# regulator_plus_switch.net
KiCad netlist of a schematic drawn in EAGLE
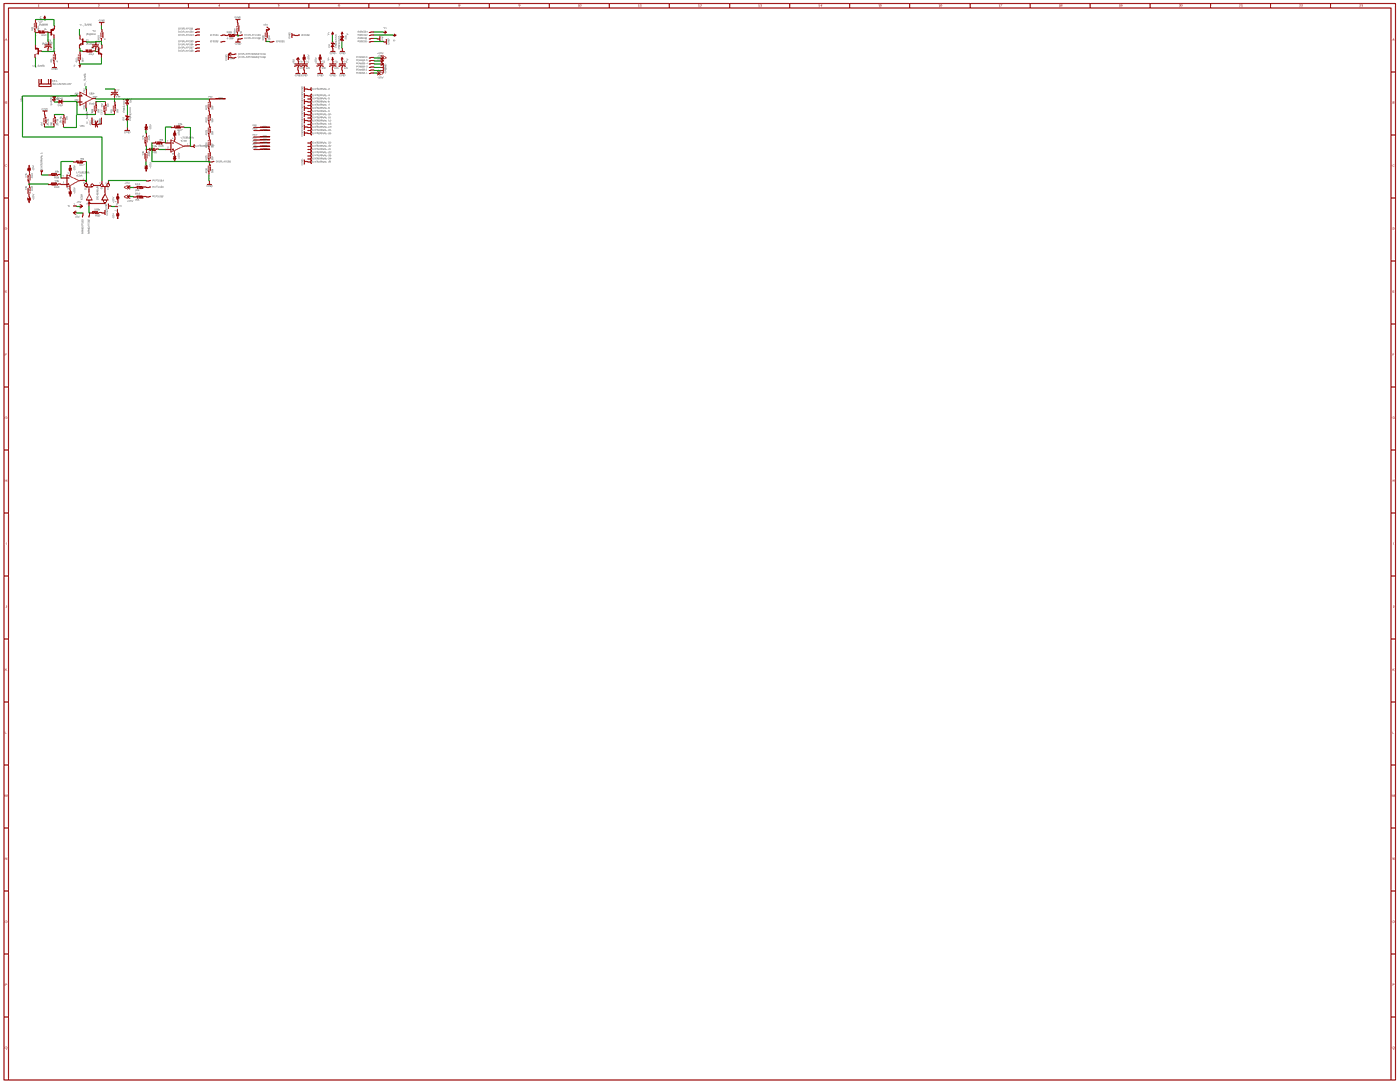
[diagram p0: schematic, sheet 1, overview]
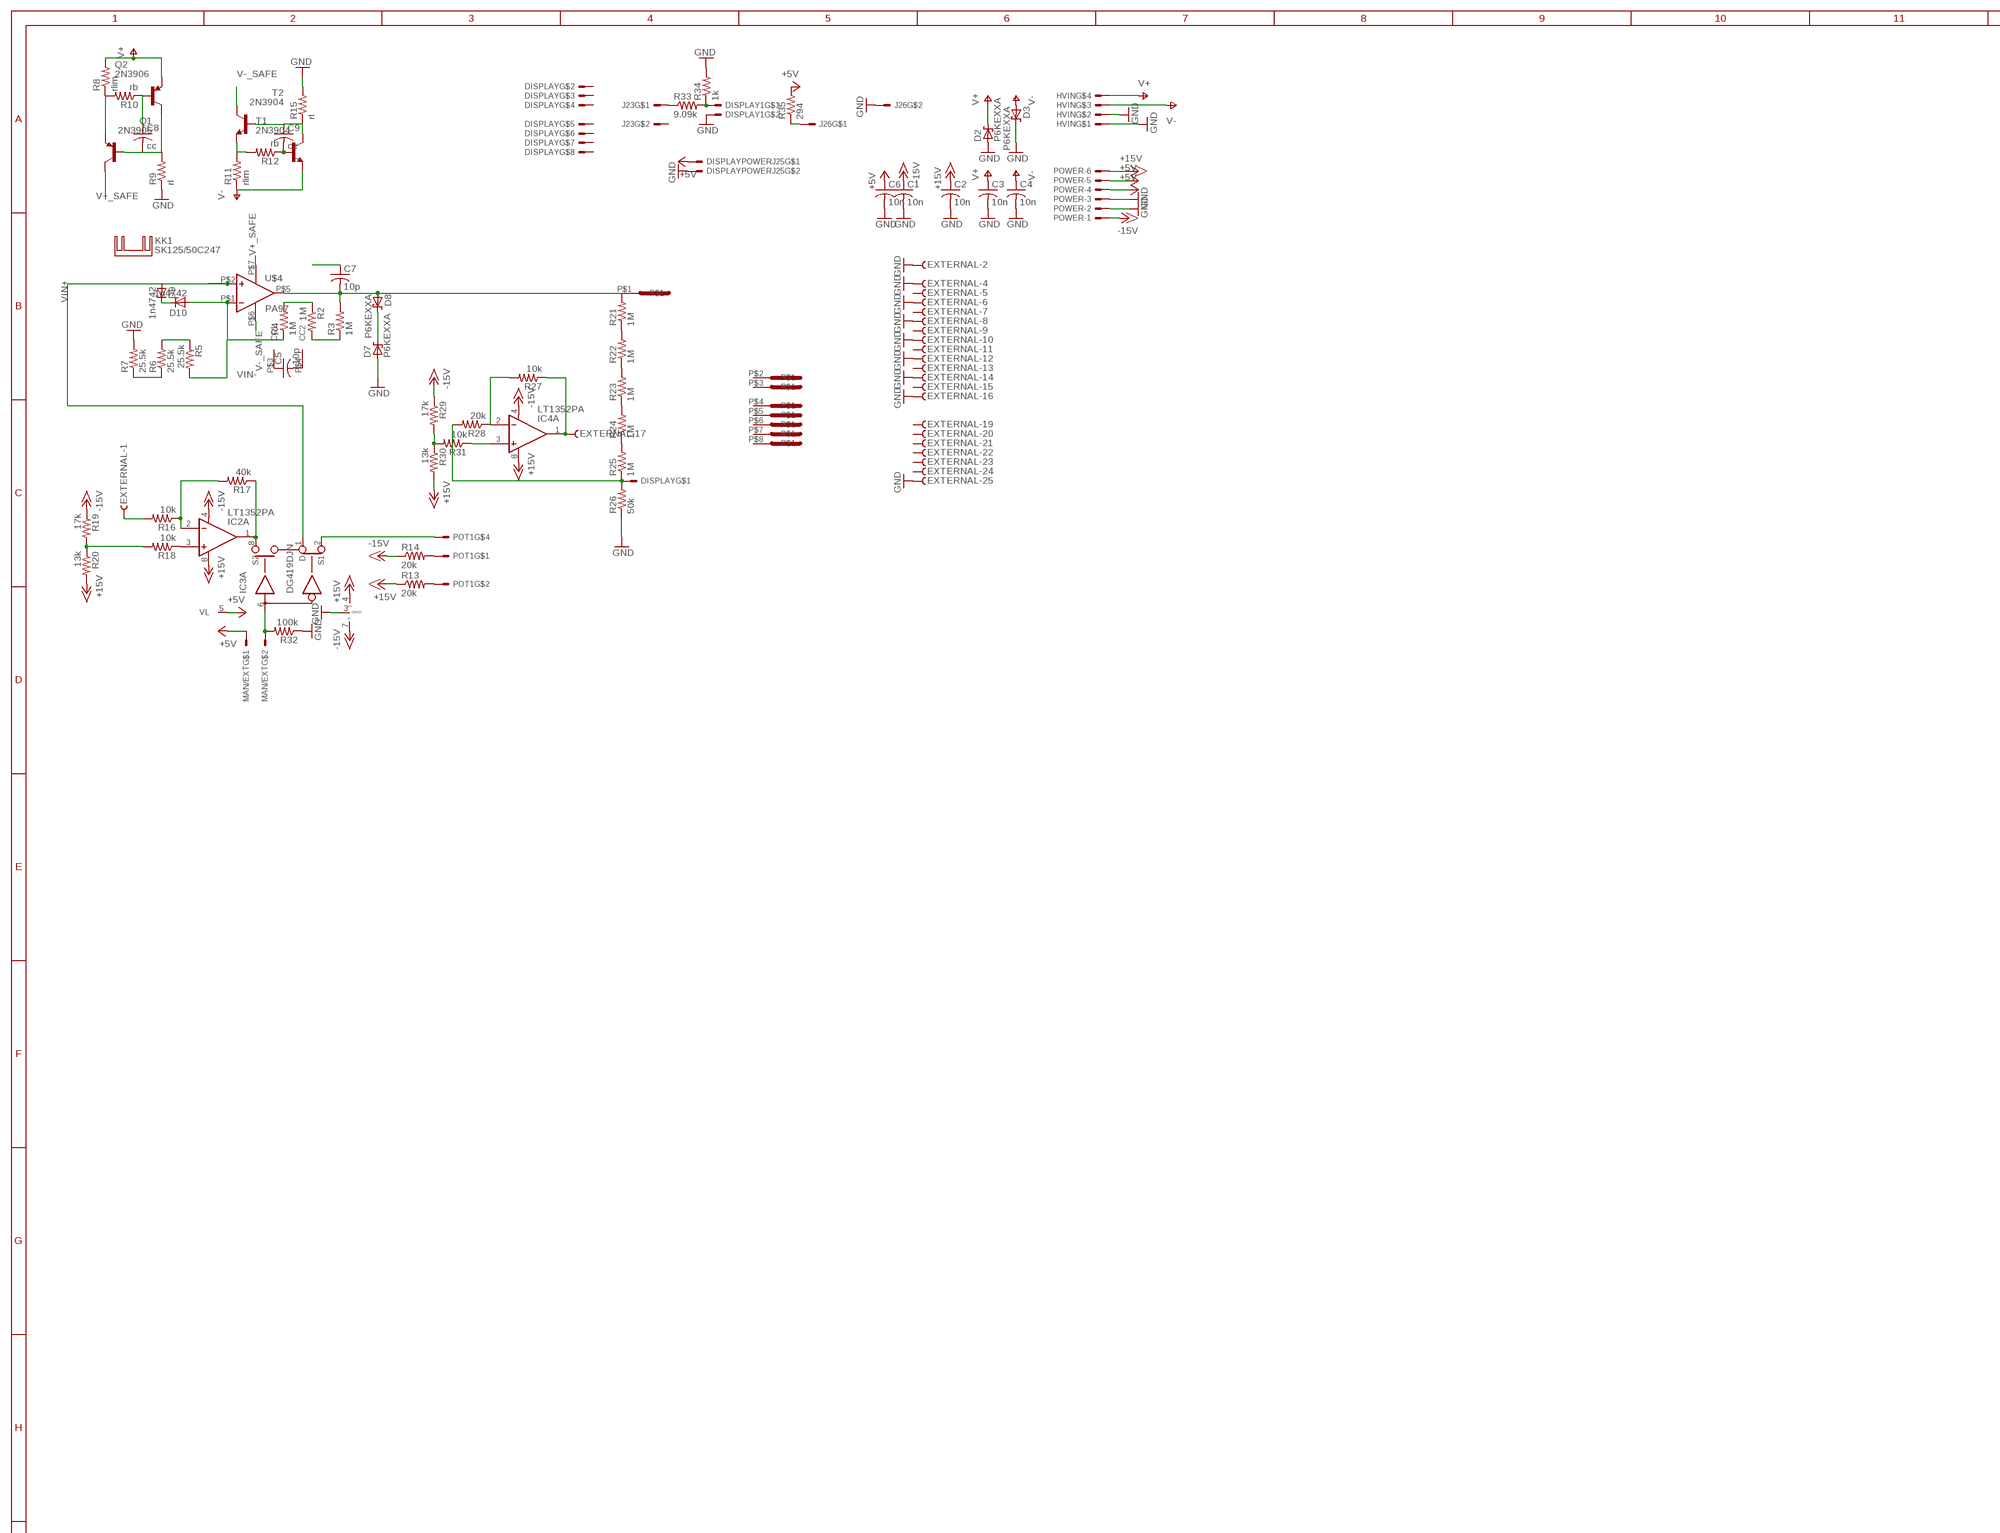
[diagram p1: schematic, sheet 1, part 1 of 5]
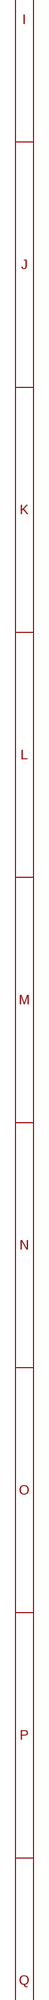
[diagram p2: schematic, sheet 1, part 2 of 5]
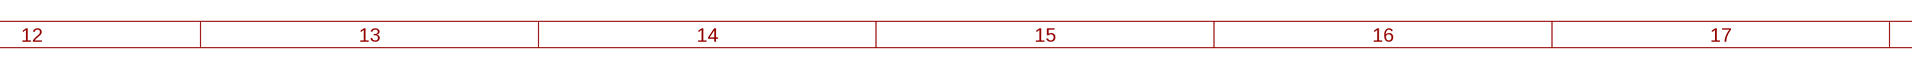
[diagram p3: schematic, sheet 1, part 3 of 5]
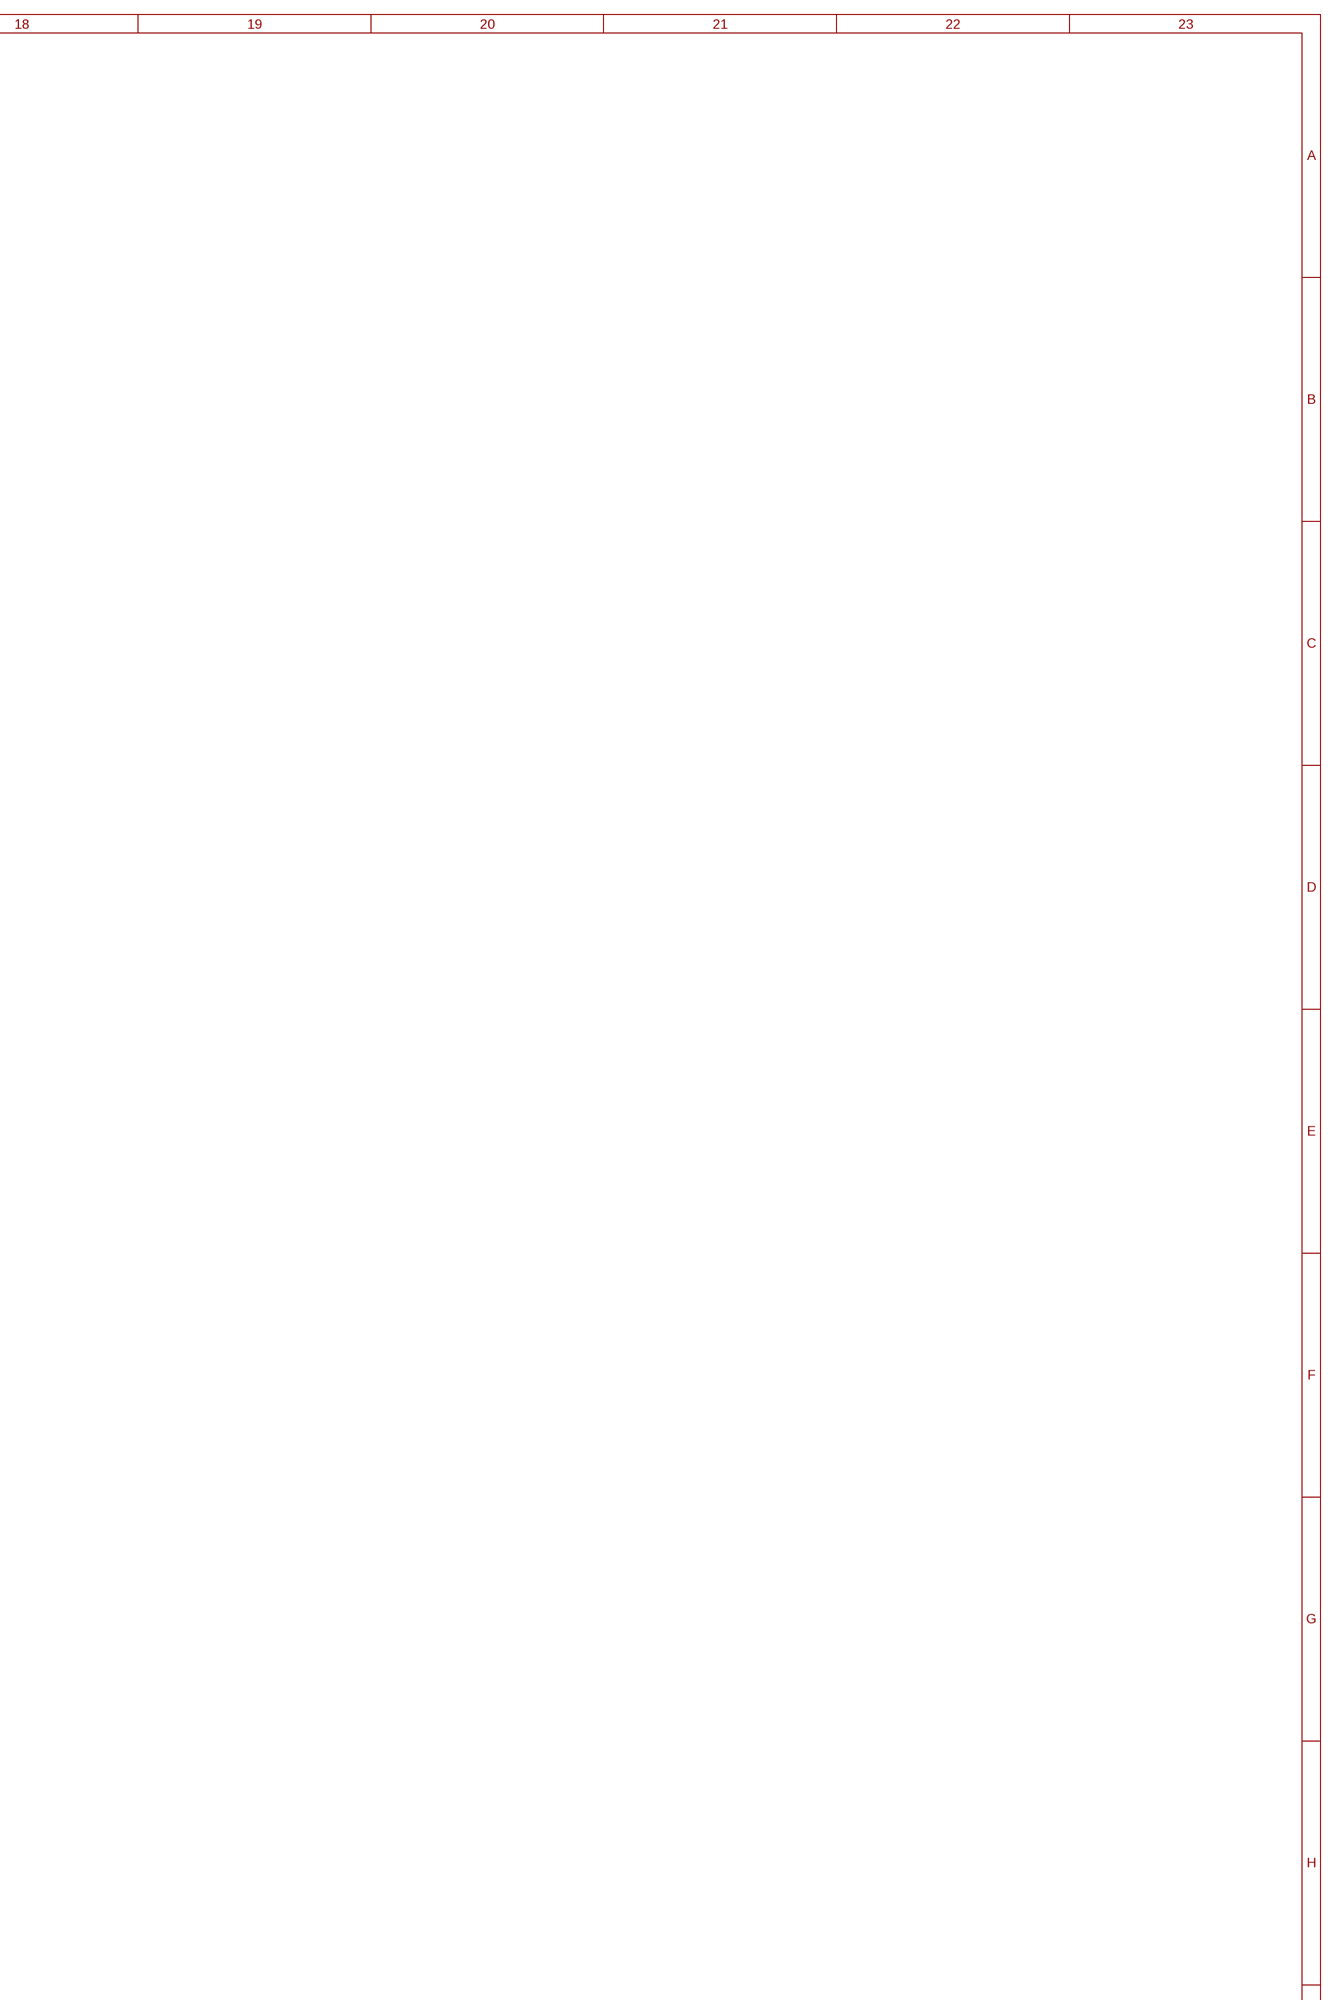
[diagram p4: schematic, sheet 1, part 4 of 5]
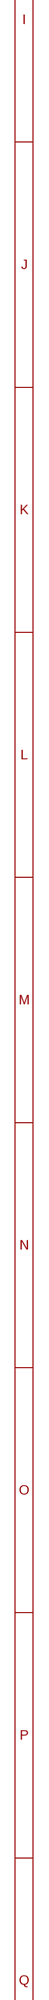
[diagram p5: schematic, sheet 1, part 5 of 5]

(export (version "E")
  (design (tool "Eeschema 10.0.6"))
  (components
    (comp (ref "C1")
      (value "10n")
      (footprint "eagle-import:C075-032X103")
      (libsource (lib "eagle-import") (part "C-US075-032X103"))
    )
    (comp (ref "C2")
      (value "10n")
      (footprint "eagle-import:C075-032X103")
      (libsource (lib "eagle-import") (part "C-US075-032X103"))
    )
    (comp (ref "C3")
      (value "10n")
      (footprint "eagle-import:C075-032X103")
      (libsource (lib "eagle-import") (part "C-US075-032X103"))
    )
    (comp (ref "C4")
      (value "10n")
      (footprint "eagle-import:C075-032X103")
      (libsource (lib "eagle-import") (part "C-US075-032X103"))
    )
    (comp (ref "C5")
      (value "10p")
      (footprint "eagle-import:C075-032X103")
      (libsource (lib "eagle-import") (part "C-US075-032X103"))
    )
    (comp (ref "C6")
      (value "10n")
      (footprint "eagle-import:C075-032X103")
      (libsource (lib "eagle-import") (part "C-US075-032X103"))
    )
    (comp (ref "C7")
      (value "10p")
      (footprint "eagle-import:C075-032X103")
      (libsource (lib "eagle-import") (part "C-US075-032X103"))
    )
    (comp (ref "C8")
      (value "cc")
      (footprint "eagle-import:C075-032X103")
      (libsource (lib "eagle-import") (part "C-US075-032X103"))
    )
    (comp (ref "C9")
      (value "cc")
      (footprint "eagle-import:C075-032X103")
      (libsource (lib "eagle-import") (part "C-US075-032X103"))
    )
    (comp (ref "D2")
      (value "P6KEXXA")
      (footprint "eagle-import:C1702-15")
      (libsource (lib "eagle-import") (part "P6KEXXA"))
    )
    (comp (ref "D3")
      (value "P6KEXXA")
      (footprint "eagle-import:C1702-15")
      (libsource (lib "eagle-import") (part "P6KEXXA"))
    )
    (comp (ref "D7")
      (value "P6KEXXA")
      (footprint "eagle-import:C1702-15")
      (libsource (lib "eagle-import") (part "P6KEXXA"))
    )
    (comp (ref "D8")
      (value "P6KEXXA")
      (footprint "eagle-import:C1702-15")
      (libsource (lib "eagle-import") (part "P6KEXXA"))
    )
    (comp (ref "D9")
      (value "1n4742")
      (footprint "eagle-import:DO41Z10")
      (libsource (lib "eagle-import") (part "ZENER-DIODEDO41Z10"))
    )
    (comp (ref "D10")
      (value "1n4742")
      (footprint "eagle-import:DO41Z10")
      (libsource (lib "eagle-import") (part "ZENER-DIODEDO41Z10"))
    )
    (comp (ref "DISPLAY")
      (value "5669-8")
      (footprint "eagle-import:5669-8")
      (libsource (lib "eagle-import") (part "5669-8"))
    )
    (comp (ref "DISPLAY1")
      (value "5569-2")
      (footprint "eagle-import:5569-2")
      (libsource (lib "eagle-import") (part "5569-2"))
    )
    (comp (ref "DISPLAYPOWERJ25")
      (value "5569-2")
      (footprint "eagle-import:5569-2")
      (libsource (lib "eagle-import") (part "5569-2"))
    )
    (comp (ref "EXTERNAL")
      (value "F25HPS")
      (footprint "eagle-import:F25HP")
      (libsource (lib "eagle-import") (part "F25?SHP"))
    )
    (comp (ref "HVIN")
      (value "5569-4")
      (footprint "eagle-import:5669-4")
      (libsource (lib "eagle-import") (part "5569-4"))
    )
    (comp (ref "IC2")
      (value "LT1352PA")
      (footprint "eagle-import:DIL08")
      (libsource (lib "eagle-import") (part "LT1352PA"))
    )
    (comp (ref "IC3")
      (value "DG419DJN")
      (footprint "eagle-import:DIL08")
      (libsource (lib "eagle-import") (part "DG419DJN"))
    )
    (comp (ref "IC4")
      (value "LT1352PA")
      (footprint "eagle-import:DIL08")
      (libsource (lib "eagle-import") (part "LT1352PA"))
    )
    (comp (ref "J23")
      (value "5569-2")
      (footprint "eagle-import:5569-2")
      (libsource (lib "eagle-import") (part "5569-2"))
    )
    (comp (ref "J26")
      (value "5569-2")
      (footprint "eagle-import:5569-2")
      (libsource (lib "eagle-import") (part "5569-2"))
    )
    (comp (ref "KK1")
      (value "SK125/50C247")
      (footprint "eagle-import:C247-050")
      (libsource (lib "eagle-import") (part "SK125/50C247"))
    )
    (comp (ref "MAN/EXT")
      (value "5569-2")
      (footprint "eagle-import:5569-2")
      (libsource (lib "eagle-import") (part "5569-2"))
    )
    (comp (ref "OUT")
      (value "640584-1")
      (footprint "eagle-import:640584-1")
      (libsource (lib "eagle-import") (part "640584-1"))
    )
    (comp (ref "POT1")
      (value "5569-4")
      (footprint "eagle-import:5669-4")
      (libsource (lib "eagle-import") (part "5569-4"))
    )
    (comp (ref "POWER")
      (value "KK-156-6")
      (footprint "eagle-import:KK-156-6")
      (libsource (lib "eagle-import") (part "KK-156-6"))
    )
    (comp (ref "Q1")
      (value "2N3906")
      (footprint "eagle-import:TO92")
      (libsource (lib "eagle-import") (part "2N3906"))
    )
    (comp (ref "Q2")
      (value "2N3906")
      (footprint "eagle-import:TO92")
      (libsource (lib "eagle-import") (part "2N3906"))
    )
    (comp (ref "R2")
      (value "1M")
      (footprint "eagle-import:0207_10")
      (libsource (lib "eagle-import") (part "R-US_0207/10"))
    )
    (comp (ref "R3")
      (value "1M")
      (footprint "eagle-import:0207_10")
      (libsource (lib "eagle-import") (part "R-US_0207/10"))
    )
    (comp (ref "R4")
      (value "1M")
      (footprint "eagle-import:0207_10")
      (libsource (lib "eagle-import") (part "R-US_0207/10"))
    )
    (comp (ref "R5")
      (value "25.5k")
      (footprint "eagle-import:0207_10")
      (libsource (lib "eagle-import") (part "R-US_0207/10"))
    )
    (comp (ref "R6")
      (value "25.5k")
      (footprint "eagle-import:0207_10")
      (libsource (lib "eagle-import") (part "R-US_0207/10"))
    )
    (comp (ref "R7")
      (value "25.5k")
      (footprint "eagle-import:0207_10")
      (libsource (lib "eagle-import") (part "R-US_0207/10"))
    )
    (comp (ref "R8")
      (value "rlim")
      (footprint "eagle-import:0207_10")
      (libsource (lib "eagle-import") (part "R-US_0207/10"))
    )
    (comp (ref "R9")
      (value "rl")
      (footprint "eagle-import:0207_10")
      (libsource (lib "eagle-import") (part "R-US_0207/10"))
    )
    (comp (ref "R10")
      (value "rb")
      (footprint "eagle-import:0207_10")
      (libsource (lib "eagle-import") (part "R-US_0207/10"))
    )
    (comp (ref "R11")
      (value "rlim")
      (footprint "eagle-import:0207_10")
      (libsource (lib "eagle-import") (part "R-US_0207/10"))
    )
    (comp (ref "R12")
      (value "rb")
      (footprint "eagle-import:0207_10")
      (libsource (lib "eagle-import") (part "R-US_0207/10"))
    )
    (comp (ref "R13")
      (value "20k")
      (footprint "eagle-import:0207_15")
      (libsource (lib "eagle-import") (part "R-US_0207/15"))
    )
    (comp (ref "R14")
      (value "20k")
      (footprint "eagle-import:0207_15")
      (libsource (lib "eagle-import") (part "R-US_0207/15"))
    )
    (comp (ref "R15")
      (value "rl")
      (footprint "eagle-import:0207_10")
      (libsource (lib "eagle-import") (part "R-US_0207/10"))
    )
    (comp (ref "R16")
      (value "10k")
      (footprint "eagle-import:0207_10")
      (libsource (lib "eagle-import") (part "R-US_0207/10"))
    )
    (comp (ref "R17")
      (value "40k")
      (footprint "eagle-import:0207_10")
      (libsource (lib "eagle-import") (part "R-US_0207/10"))
    )
    (comp (ref "R18")
      (value "10k")
      (footprint "eagle-import:0207_10")
      (libsource (lib "eagle-import") (part "R-US_0207/10"))
    )
    (comp (ref "R19")
      (value "17k")
      (footprint "eagle-import:0207_10")
      (libsource (lib "eagle-import") (part "R-US_0207/10"))
    )
    (comp (ref "R20")
      (value "13k")
      (footprint "eagle-import:0207_10")
      (libsource (lib "eagle-import") (part "R-US_0207/10"))
    )
    (comp (ref "R21")
      (value "1M")
      (footprint "eagle-import:0207_10")
      (libsource (lib "eagle-import") (part "resistor_R-US_0207/10"))
    )
    (comp (ref "R22")
      (value "1M")
      (footprint "eagle-import:0207_10")
      (libsource (lib "eagle-import") (part "resistor_R-US_0207/10"))
    )
    (comp (ref "R23")
      (value "1M")
      (footprint "eagle-import:0207_10")
      (libsource (lib "eagle-import") (part "resistor_R-US_0207/10"))
    )
    (comp (ref "R24")
      (value "1M")
      (footprint "eagle-import:0207_10")
      (libsource (lib "eagle-import") (part "resistor_R-US_0207/10"))
    )
    (comp (ref "R25")
      (value "1M")
      (footprint "eagle-import:0207_10")
      (libsource (lib "eagle-import") (part "resistor_R-US_0207/10"))
    )
    (comp (ref "R26")
      (value "50k")
      (footprint "eagle-import:0207_10")
      (libsource (lib "eagle-import") (part "R-US_0207/10"))
    )
    (comp (ref "R27")
      (value "10k")
      (footprint "eagle-import:0207_10")
      (libsource (lib "eagle-import") (part "R-US_0207/10"))
    )
    (comp (ref "R28")
      (value "20k")
      (footprint "eagle-import:0207_10")
      (libsource (lib "eagle-import") (part "R-US_0207/10"))
    )
    (comp (ref "R29")
      (value "17k")
      (footprint "eagle-import:0207_10")
      (libsource (lib "eagle-import") (part "R-US_0207/10"))
    )
    (comp (ref "R30")
      (value "13k")
      (footprint "eagle-import:0207_10")
      (libsource (lib "eagle-import") (part "R-US_0207/10"))
    )
    (comp (ref "R31")
      (value "10k")
      (footprint "eagle-import:0207_10")
      (libsource (lib "eagle-import") (part "R-US_0207/10"))
    )
    (comp (ref "R32")
      (value "100k")
      (footprint "eagle-import:0207_15")
      (libsource (lib "eagle-import") (part "R-US_0207/15"))
    )
    (comp (ref "R33")
      (value "9.09k")
      (footprint "eagle-import:0207_10")
      (libsource (lib "eagle-import") (part "R-US_0207/10"))
    )
    (comp (ref "R34")
      (value "1k")
      (footprint "eagle-import:0207_10")
      (libsource (lib "eagle-import") (part "R-US_0207/10"))
    )
    (comp (ref "R35")
      (value "294")
      (footprint "eagle-import:0207_10")
      (libsource (lib "eagle-import") (part "R-US_0207/10"))
    )
    (comp (ref "T1")
      (value "2N3904")
      (footprint "eagle-import:TO92")
      (libsource (lib "eagle-import") (part "2N3904"))
    )
    (comp (ref "T2")
      (value "2N3904")
      (footprint "eagle-import:TO92")
      (libsource (lib "eagle-import") (part "2N3904"))
    )
    (comp (ref "U$4")
      (value "PA97")
      (footprint "eagle-import:7SIP")
      (libsource (lib "eagle-import") (part "PA97"))
    )
  )
  (nets
    (net (code "1") (name "+5V") (class "Default")
      (node (ref "C6") (pin "1") (pinfunction "1_1") (pintype "passive"))
      (node (ref "DISPLAYPOWERJ25") (pin "P$1") (pinfunction "S_P$1") (pintype "passive"))
      (node (ref "IC3") (pin "5") (pinfunction "VL_5") (pintype "input"))
      (node (ref "MAN/EXT") (pin "P$1") (pinfunction "S_P$1") (pintype "passive"))
      (node (ref "POWER") (pin "4") (pinfunction "S_4") (pintype "passive"))
      (node (ref "POWER") (pin "5") (pinfunction "S_5") (pintype "passive"))
      (node (ref "R35") (pin "2") (pinfunction "2_2") (pintype "passive"))
    )
    (net (code "2") (name "+15V") (class "Default")
      (node (ref "C2") (pin "1") (pinfunction "1_1") (pintype "passive"))
      (node (ref "IC2") (pin "8") (pinfunction "V+_8") (pintype "power_in"))
      (node (ref "IC3") (pin "4") (pinfunction "V+_4") (pintype "power_in"))
      (node (ref "IC4") (pin "8") (pinfunction "V+_8") (pintype "power_in"))
      (node (ref "POWER") (pin "6") (pinfunction "S_6") (pintype "passive"))
      (node (ref "R13") (pin "1") (pinfunction "1_1") (pintype "passive"))
      (node (ref "R20") (pin "2") (pinfunction "2_2") (pintype "passive"))
      (node (ref "R30") (pin "2") (pinfunction "2_2") (pintype "passive"))
    )
    (net (code "3") (name "-15V") (class "Default")
      (node (ref "C1") (pin "1") (pinfunction "1_1") (pintype "passive"))
      (node (ref "IC2") (pin "4") (pinfunction "V-_4") (pintype "power_in"))
      (node (ref "IC3") (pin "7") (pinfunction "V-_7") (pintype "power_in"))
      (node (ref "IC4") (pin "4") (pinfunction "V-_4") (pintype "power_in"))
      (node (ref "POWER") (pin "1") (pinfunction "S_1") (pintype "passive"))
      (node (ref "R14") (pin "1") (pinfunction "1_1") (pintype "passive"))
      (node (ref "R19") (pin "1") (pinfunction "1_1") (pintype "passive"))
      (node (ref "R29") (pin "1") (pinfunction "1_1") (pintype "passive"))
    )
    (net (code "4") (name "/V+_SAFE") (class "Default")
      (node (ref "Q1") (pin "1") (pinfunction "C_1") (pintype "passive"))
      (node (ref "U$4") (pin "P$7") (pinfunction "V+_P$7") (pintype "power_in"))
    )
    (net (code "5") (name "/V-_SAFE") (class "Default")
      (node (ref "T2") (pin "1") (pinfunction "C_1") (pintype "passive"))
      (node (ref "U$4") (pin "P$6") (pinfunction "V-_P$6") (pintype "power_in"))
    )
    (net (code "6") (name "/VIN+") (class "Default")
      (node (ref "D9") (pin "A") (pinfunction "A_A") (pintype "passive"))
      (node (ref "IC3") (pin "1") (pinfunction "D_1") (pintype "bidirectional"))
      (node (ref "U$4") (pin "P$2") (pinfunction "+IN_P$2") (pintype "input"))
    )
    (net (code "7") (name "/VIN-") (class "Default")
      (node (ref "C7") (pin "1") (pinfunction "1_1") (pintype "passive"))
      (node (ref "D10") (pin "A") (pinfunction "A_A") (pintype "passive"))
      (node (ref "R4") (pin "1") (pinfunction "1_1") (pintype "passive"))
      (node (ref "R5") (pin "2") (pinfunction "2_2") (pintype "passive"))
      (node (ref "U$4") (pin "P$1") (pinfunction "-IN_P$1") (pintype "input"))
    )
    (net (code "8") (name "GND") (class "Default")
      (node (ref "C1") (pin "2") (pinfunction "2_2") (pintype "passive"))
      (node (ref "C2") (pin "2") (pinfunction "2_2") (pintype "passive"))
      (node (ref "C3") (pin "2") (pinfunction "2_2") (pintype "passive"))
      (node (ref "C4") (pin "2") (pinfunction "2_2") (pintype "passive"))
      (node (ref "C6") (pin "2") (pinfunction "2_2") (pintype "passive"))
      (node (ref "D2") (pin "A") (pinfunction "A_A") (pintype "passive"))
      (node (ref "D3") (pin "C") (pinfunction "C_C") (pintype "passive"))
      (node (ref "D7") (pin "A") (pinfunction "A_A") (pintype "passive"))
      (node (ref "DISPLAY1") (pin "P$2") (pinfunction "S_P$2") (pintype "passive"))
      (node (ref "DISPLAYPOWERJ25") (pin "P$2") (pinfunction "S_P$2") (pintype "passive"))
      (node (ref "EXTERNAL") (pin "10") (pinfunction "F_10") (pintype "passive"))
      (node (ref "EXTERNAL") (pin "12") (pinfunction "F_12") (pintype "passive"))
      (node (ref "EXTERNAL") (pin "14") (pinfunction "F_14") (pintype "passive"))
      (node (ref "EXTERNAL") (pin "16") (pinfunction "F_16") (pintype "passive"))
      (node (ref "EXTERNAL") (pin "2") (pinfunction "F_2") (pintype "passive"))
      (node (ref "EXTERNAL") (pin "25") (pinfunction "F_25") (pintype "passive"))
      (node (ref "EXTERNAL") (pin "4") (pinfunction "F_4") (pintype "passive"))
      (node (ref "EXTERNAL") (pin "6") (pinfunction "F_6") (pintype "passive"))
      (node (ref "EXTERNAL") (pin "8") (pinfunction "F_8") (pintype "passive"))
      (node (ref "HVIN") (pin "P$1") (pinfunction "S_P$1") (pintype "passive"))
      (node (ref "HVIN") (pin "P$2") (pinfunction "S_P$2") (pintype "passive"))
      (node (ref "IC3") (pin "3") (pinfunction "GND_3") (pintype "power_in"))
      (node (ref "J26") (pin "P$2") (pinfunction "S_P$2") (pintype "passive"))
      (node (ref "POWER") (pin "2") (pinfunction "S_2") (pintype "passive"))
      (node (ref "POWER") (pin "3") (pinfunction "S_3") (pintype "passive"))
      (node (ref "R15") (pin "2") (pinfunction "2_2") (pintype "passive"))
      (node (ref "R26") (pin "1") (pinfunction "1_1") (pintype "passive"))
      (node (ref "R32") (pin "1") (pinfunction "1_1") (pintype "passive"))
      (node (ref "R34") (pin "2") (pinfunction "2_2") (pintype "passive"))
      (node (ref "R7") (pin "2") (pinfunction "2_2") (pintype "passive"))
      (node (ref "R9") (pin "1") (pinfunction "1_1") (pintype "passive"))
    )
    (net (code "9") (name "Net-(D7-PadC)") (class "Default")
      (node (ref "D7") (pin "C") (pinfunction "C_C") (pintype "passive"))
      (node (ref "D8") (pin "C") (pinfunction "C_C") (pintype "passive"))
    )
    (net (code "10") (name "Net-(D10-PadC)") (class "Default")
      (node (ref "D10") (pin "C") (pinfunction "C_C") (pintype "passive"))
      (node (ref "D9") (pin "C") (pinfunction "C_C") (pintype "passive"))
    )
    (net (code "11") (name "Net-(DISPLAY1A-S)") (class "Default")
      (node (ref "DISPLAY1") (pin "P$1") (pinfunction "S_P$1") (pintype "passive"))
      (node (ref "R33") (pin "2") (pinfunction "2_2") (pintype "passive"))
      (node (ref "R34") (pin "1") (pinfunction "1_1") (pintype "passive"))
    )
    (net (code "12") (name "Net-(DISPLAYA-S)") (class "Default")
      (node (ref "DISPLAY") (pin "P$1") (pinfunction "S_P$1") (pintype "passive"))
      (node (ref "R25") (pin "1") (pinfunction "1_1") (pintype "passive"))
      (node (ref "R26") (pin "2") (pinfunction "2_2") (pintype "passive"))
      (node (ref "R28") (pin "2") (pinfunction "2_2") (pintype "passive"))
    )
    (net (code "13") (name "Net-(EXTERNALA-F)") (class "Default")
      (node (ref "EXTERNAL") (pin "1") (pinfunction "F_1") (pintype "passive"))
      (node (ref "R16") (pin "2") (pinfunction "2_2") (pintype "passive"))
    )
    (net (code "14") (name "Net-(EXTERNALI-F)") (class "Default")
      (node (ref "EXTERNAL") (pin "17") (pinfunction "F_17") (pintype "passive"))
      (node (ref "IC4") (pin "1") (pinfunction "OUT_1") (pintype "output"))
      (node (ref "R27") (pin "1") (pinfunction "1_1") (pintype "passive"))
    )
    (net (code "15") (name "Net-(IC2A-+IN)") (class "Default")
      (node (ref "IC2") (pin "3") (pinfunction "+IN_3") (pintype "input"))
      (node (ref "R18") (pin "1") (pinfunction "1_1") (pintype "passive"))
    )
    (net (code "16") (name "Net-(IC2A--IN)") (class "Default")
      (node (ref "IC2") (pin "2") (pinfunction "-IN_2") (pintype "input"))
      (node (ref "R16") (pin "1") (pinfunction "1_1") (pintype "passive"))
      (node (ref "R17") (pin "2") (pinfunction "2_2") (pintype "passive"))
    )
    (net (code "17") (name "Net-(IC2A-OUT)") (class "Default")
      (node (ref "IC2") (pin "1") (pinfunction "OUT_1") (pintype "output"))
      (node (ref "IC3") (pin "8") (pinfunction "S2_8") (pintype "bidirectional"))
      (node (ref "R17") (pin "1") (pinfunction "1_1") (pintype "passive"))
    )
    (net (code "18") (name "Net-(IC3A-IN)") (class "Default")
      (node (ref "IC3") (pin "6") (pinfunction "IN_6") (pintype "input"))
      (node (ref "MAN/EXT") (pin "P$2") (pinfunction "S_P$2") (pintype "passive"))
      (node (ref "R32") (pin "2") (pinfunction "2_2") (pintype "passive"))
    )
    (net (code "19") (name "Net-(IC3A-S1)") (class "Default")
      (node (ref "IC3") (pin "2") (pinfunction "S1_2") (pintype "bidirectional"))
      (node (ref "POT1") (pin "P$4") (pinfunction "S_P$4") (pintype "passive"))
    )
    (net (code "20") (name "Net-(IC4A-+IN)") (class "Default")
      (node (ref "IC4") (pin "3") (pinfunction "+IN_3") (pintype "input"))
      (node (ref "R31") (pin "1") (pinfunction "1_1") (pintype "passive"))
    )
    (net (code "21") (name "Net-(IC4A--IN)") (class "Default")
      (node (ref "IC4") (pin "2") (pinfunction "-IN_2") (pintype "input"))
      (node (ref "R27") (pin "2") (pinfunction "2_2") (pintype "passive"))
      (node (ref "R28") (pin "1") (pinfunction "1_1") (pintype "passive"))
    )
    (net (code "22") (name "Net-(J23A-S)") (class "Default")
      (node (ref "J23") (pin "P$1") (pinfunction "S_P$1") (pintype "passive"))
      (node (ref "R33") (pin "1") (pinfunction "1_1") (pintype "passive"))
    )
    (net (code "23") (name "Net-(J26A-S)") (class "Default")
      (node (ref "J26") (pin "P$1") (pinfunction "S_P$1") (pintype "passive"))
      (node (ref "R35") (pin "1") (pinfunction "1_1") (pintype "passive"))
    )
    (net (code "24") (name "Net-(POT1A-S)") (class "Default")
      (node (ref "POT1") (pin "P$1") (pinfunction "S_P$1") (pintype "passive"))
      (node (ref "R14") (pin "2") (pinfunction "2_2") (pintype "passive"))
    )
    (net (code "25") (name "Net-(POT1B-S)") (class "Default")
      (node (ref "POT1") (pin "P$2") (pinfunction "S_P$2") (pintype "passive"))
      (node (ref "R13") (pin "2") (pinfunction "2_2") (pintype "passive"))
    )
    (net (code "26") (name "Net-(Q1-B)") (class "Default")
      (node (ref "C8") (pin "2") (pinfunction "2_2") (pintype "passive"))
      (node (ref "Q1") (pin "2") (pinfunction "B_2") (pintype "passive"))
      (node (ref "Q2") (pin "1") (pinfunction "C_1") (pintype "passive"))
      (node (ref "R9") (pin "2") (pinfunction "2_2") (pintype "passive"))
    )
    (net (code "27") (name "Net-(Q1-E)") (class "Default")
      (node (ref "Q1") (pin "3") (pinfunction "E_3") (pintype "passive"))
      (node (ref "R10") (pin "2") (pinfunction "2_2") (pintype "passive"))
      (node (ref "R8") (pin "1") (pinfunction "1_1") (pintype "passive"))
    )
    (net (code "28") (name "Net-(Q2-B)") (class "Default")
      (node (ref "C8") (pin "1") (pinfunction "1_1") (pintype "passive"))
      (node (ref "Q2") (pin "2") (pinfunction "B_2") (pintype "passive"))
      (node (ref "R10") (pin "1") (pinfunction "1_1") (pintype "passive"))
    )
    (net (code "29") (name "Net-(R2-Pad1)") (class "Default")
      (node (ref "R2") (pin "1") (pinfunction "1_1") (pintype "passive"))
      (node (ref "R4") (pin "2") (pinfunction "2_2") (pintype "passive"))
    )
    (net (code "30") (name "Net-(R2-Pad2)") (class "Default")
      (node (ref "R2") (pin "2") (pinfunction "2_2") (pintype "passive"))
      (node (ref "R3") (pin "1") (pinfunction "1_1") (pintype "passive"))
    )
    (net (code "31") (name "Net-(R5-Pad1)") (class "Default")
      (node (ref "R5") (pin "1") (pinfunction "1_1") (pintype "passive"))
      (node (ref "R6") (pin "2") (pinfunction "2_2") (pintype "passive"))
    )
    (net (code "32") (name "Net-(R6-Pad1)") (class "Default")
      (node (ref "R6") (pin "1") (pinfunction "1_1") (pintype "passive"))
      (node (ref "R7") (pin "1") (pinfunction "1_1") (pintype "passive"))
    )
    (net (code "33") (name "Net-(R18-Pad2)") (class "Default")
      (node (ref "R18") (pin "2") (pinfunction "2_2") (pintype "passive"))
      (node (ref "R19") (pin "2") (pinfunction "2_2") (pintype "passive"))
      (node (ref "R20") (pin "1") (pinfunction "1_1") (pintype "passive"))
    )
    (net (code "34") (name "Net-(R21-Pad1)") (class "Default")
      (node (ref "R21") (pin "1") (pinfunction "1_1") (pintype "passive"))
      (node (ref "R22") (pin "2") (pinfunction "2_2") (pintype "passive"))
    )
    (net (code "35") (name "Net-(R22-Pad1)") (class "Default")
      (node (ref "R22") (pin "1") (pinfunction "1_1") (pintype "passive"))
      (node (ref "R23") (pin "2") (pinfunction "2_2") (pintype "passive"))
    )
    (net (code "36") (name "Net-(R23-Pad1)") (class "Default")
      (node (ref "R23") (pin "1") (pinfunction "1_1") (pintype "passive"))
      (node (ref "R24") (pin "2") (pinfunction "2_2") (pintype "passive"))
    )
    (net (code "37") (name "Net-(R24-Pad1)") (class "Default")
      (node (ref "R24") (pin "1") (pinfunction "1_1") (pintype "passive"))
      (node (ref "R25") (pin "2") (pinfunction "2_2") (pintype "passive"))
    )
    (net (code "38") (name "Net-(R29-Pad2)") (class "Default")
      (node (ref "R29") (pin "2") (pinfunction "2_2") (pintype "passive"))
      (node (ref "R30") (pin "1") (pinfunction "1_1") (pintype "passive"))
      (node (ref "R31") (pin "2") (pinfunction "2_2") (pintype "passive"))
    )
    (net (code "39") (name "Net-(T1-B)") (class "Default")
      (node (ref "C9") (pin "2") (pinfunction "2_2") (pintype "passive"))
      (node (ref "R12") (pin "1") (pinfunction "1_1") (pintype "passive"))
      (node (ref "T1") (pin "2") (pinfunction "B_2") (pintype "passive"))
    )
    (net (code "40") (name "Net-(T1-C)") (class "Default")
      (node (ref "C9") (pin "1") (pinfunction "1_1") (pintype "passive"))
      (node (ref "R15") (pin "1") (pinfunction "1_1") (pintype "passive"))
      (node (ref "T1") (pin "1") (pinfunction "C_1") (pintype "passive"))
      (node (ref "T2") (pin "2") (pinfunction "B_2") (pintype "passive"))
    )
    (net (code "41") (name "Net-(T2-E)") (class "Default")
      (node (ref "R11") (pin "2") (pinfunction "2_2") (pintype "passive"))
      (node (ref "R12") (pin "2") (pinfunction "2_2") (pintype "passive"))
      (node (ref "T2") (pin "3") (pinfunction "E_3") (pintype "passive"))
    )
    (net (code "42") (name "Net-(U$4-CC1)") (class "Default")
      (node (ref "C5") (pin "1") (pinfunction "1_1") (pintype "passive"))
      (node (ref "U$4") (pin "P$3") (pinfunction "CC1_P$3") (pintype "bidirectional"))
    )
    (net (code "43") (name "Net-(U$4-CC2)") (class "Default")
      (node (ref "C5") (pin "2") (pinfunction "2_2") (pintype "passive"))
      (node (ref "U$4") (pin "P$4") (pinfunction "CC2_P$4") (pintype "bidirectional"))
    )
    (net (code "44") (name "Net-(U$4-OUT)") (class "Default")
      (node (ref "C7") (pin "2") (pinfunction "2_2") (pintype "passive"))
      (node (ref "D8") (pin "A") (pinfunction "A_A") (pintype "passive"))
      (node (ref "OUT") (pin "P$1") (pinfunction "P$1_P$1") (pintype "bidirectional"))
      (node (ref "R21") (pin "2") (pinfunction "2_2") (pintype "passive"))
      (node (ref "R3") (pin "2") (pinfunction "2_2") (pintype "passive"))
      (node (ref "U$4") (pin "P$5") (pinfunction "OUT_P$5") (pintype "output"))
    )
    (net (code "45") (name "V+") (class "Default")
      (node (ref "C3") (pin "1") (pinfunction "1_1") (pintype "passive"))
      (node (ref "D2") (pin "C") (pinfunction "C_C") (pintype "passive"))
      (node (ref "HVIN") (pin "P$4") (pinfunction "S_P$4") (pintype "passive"))
      (node (ref "Q2") (pin "3") (pinfunction "E_3") (pintype "passive"))
      (node (ref "R8") (pin "2") (pinfunction "2_2") (pintype "passive"))
    )
    (net (code "46") (name "V-") (class "Default")
      (node (ref "C4") (pin "1") (pinfunction "1_1") (pintype "passive"))
      (node (ref "D3") (pin "A") (pinfunction "A_A") (pintype "passive"))
      (node (ref "HVIN") (pin "P$3") (pinfunction "S_P$3") (pintype "passive"))
      (node (ref "R11") (pin "1") (pinfunction "1_1") (pintype "passive"))
      (node (ref "T1") (pin "3") (pinfunction "E_3") (pintype "passive"))
    )
    (net (code "47") (name "unconnected-(DISPLAYB-S-PadP$2)") (class "Default")
      (node (ref "DISPLAY") (pin "P$2") (pinfunction "S_P$2") (pintype "passive"))
    )
    (net (code "48") (name "unconnected-(DISPLAYC-S-PadP$3)") (class "Default")
      (node (ref "DISPLAY") (pin "P$3") (pinfunction "S_P$3") (pintype "passive"))
    )
    (net (code "49") (name "unconnected-(DISPLAYD-S-PadP$4)") (class "Default")
      (node (ref "DISPLAY") (pin "P$4") (pinfunction "S_P$4") (pintype "passive"))
    )
    (net (code "50") (name "unconnected-(DISPLAYE-S-PadP$5)") (class "Default")
      (node (ref "DISPLAY") (pin "P$5") (pinfunction "S_P$5") (pintype "passive"))
    )
    (net (code "51") (name "unconnected-(DISPLAYF-S-PadP$6)") (class "Default")
      (node (ref "DISPLAY") (pin "P$6") (pinfunction "S_P$6") (pintype "passive"))
    )
    (net (code "52") (name "unconnected-(DISPLAYG-S-PadP$7)") (class "Default")
      (node (ref "DISPLAY") (pin "P$7") (pinfunction "S_P$7") (pintype "passive"))
    )
    (net (code "53") (name "unconnected-(DISPLAYH-S-PadP$8)") (class "Default")
      (node (ref "DISPLAY") (pin "P$8") (pinfunction "S_P$8") (pintype "passive"))
    )
    (net (code "54") (name "unconnected-(EXTERNALC-F-Pad11)") (class "Default")
      (node (ref "EXTERNAL") (pin "11") (pinfunction "F_11") (pintype "passive"))
    )
    (net (code "55") (name "unconnected-(EXTERNALE-F-Pad13)") (class "Default")
      (node (ref "EXTERNAL") (pin "13") (pinfunction "F_13") (pintype "passive"))
    )
    (net (code "56") (name "unconnected-(EXTERNALG-F-Pad15)") (class "Default")
      (node (ref "EXTERNAL") (pin "15") (pinfunction "F_15") (pintype "passive"))
    )
    (net (code "57") (name "unconnected-(EXTERNALK-F-Pad19)") (class "Default")
      (node (ref "EXTERNAL") (pin "19") (pinfunction "F_19") (pintype "passive"))
    )
    (net (code "58") (name "unconnected-(EXTERNALM-F-Pad20)") (class "Default")
      (node (ref "EXTERNAL") (pin "20") (pinfunction "F_20") (pintype "passive"))
    )
    (net (code "59") (name "unconnected-(EXTERNALN-F-Pad21)") (class "Default")
      (node (ref "EXTERNAL") (pin "21") (pinfunction "F_21") (pintype "passive"))
    )
    (net (code "60") (name "unconnected-(EXTERNALO-F-Pad22)") (class "Default")
      (node (ref "EXTERNAL") (pin "22") (pinfunction "F_22") (pintype "passive"))
    )
    (net (code "61") (name "unconnected-(EXTERNALP-F-Pad23)") (class "Default")
      (node (ref "EXTERNAL") (pin "23") (pinfunction "F_23") (pintype "passive"))
    )
    (net (code "62") (name "unconnected-(EXTERNALQ-F-Pad24)") (class "Default")
      (node (ref "EXTERNAL") (pin "24") (pinfunction "F_24") (pintype "passive"))
    )
    (net (code "63") (name "unconnected-(EXTERNALU-F-Pad5)") (class "Default")
      (node (ref "EXTERNAL") (pin "5") (pinfunction "F_5") (pintype "passive"))
    )
    (net (code "64") (name "unconnected-(EXTERNALW-F-Pad7)") (class "Default")
      (node (ref "EXTERNAL") (pin "7") (pinfunction "F_7") (pintype "passive"))
    )
    (net (code "65") (name "unconnected-(EXTERNALY-F-Pad9)") (class "Default")
      (node (ref "EXTERNAL") (pin "9") (pinfunction "F_9") (pintype "passive"))
    )
    (net (code "66") (name "unconnected-(J23B-S-PadP$2)") (class "Default")
      (node (ref "J23") (pin "P$2") (pinfunction "S_P$2") (pintype "passive"))
    )
    (net (code "67") (name "unconnected-(OUTB-P$1-PadP$2)") (class "Default")
      (node (ref "OUT") (pin "P$2") (pinfunction "P$1_P$2") (pintype "bidirectional"))
    )
    (net (code "68") (name "unconnected-(OUTC-P$1-PadP$3)") (class "Default")
      (node (ref "OUT") (pin "P$3") (pinfunction "P$1_P$3") (pintype "bidirectional"))
    )
    (net (code "69") (name "unconnected-(OUTD-P$1-PadP$4)") (class "Default")
      (node (ref "OUT") (pin "P$4") (pinfunction "P$1_P$4") (pintype "bidirectional"))
    )
    (net (code "70") (name "unconnected-(OUTE-P$1-PadP$5)") (class "Default")
      (node (ref "OUT") (pin "P$5") (pinfunction "P$1_P$5") (pintype "bidirectional"))
    )
    (net (code "71") (name "unconnected-(OUTF-P$1-PadP$6)") (class "Default")
      (node (ref "OUT") (pin "P$6") (pinfunction "P$1_P$6") (pintype "bidirectional"))
    )
    (net (code "72") (name "unconnected-(OUTG-P$1-PadP$7)") (class "Default")
      (node (ref "OUT") (pin "P$7") (pinfunction "P$1_P$7") (pintype "bidirectional"))
    )
    (net (code "73") (name "unconnected-(OUTH-P$1-PadP$8)") (class "Default")
      (node (ref "OUT") (pin "P$8") (pinfunction "P$1_P$8") (pintype "bidirectional"))
    )
  )
)
